# ft232rl_breakout.net
KiCad netlist of a schematic drawn in EAGLE
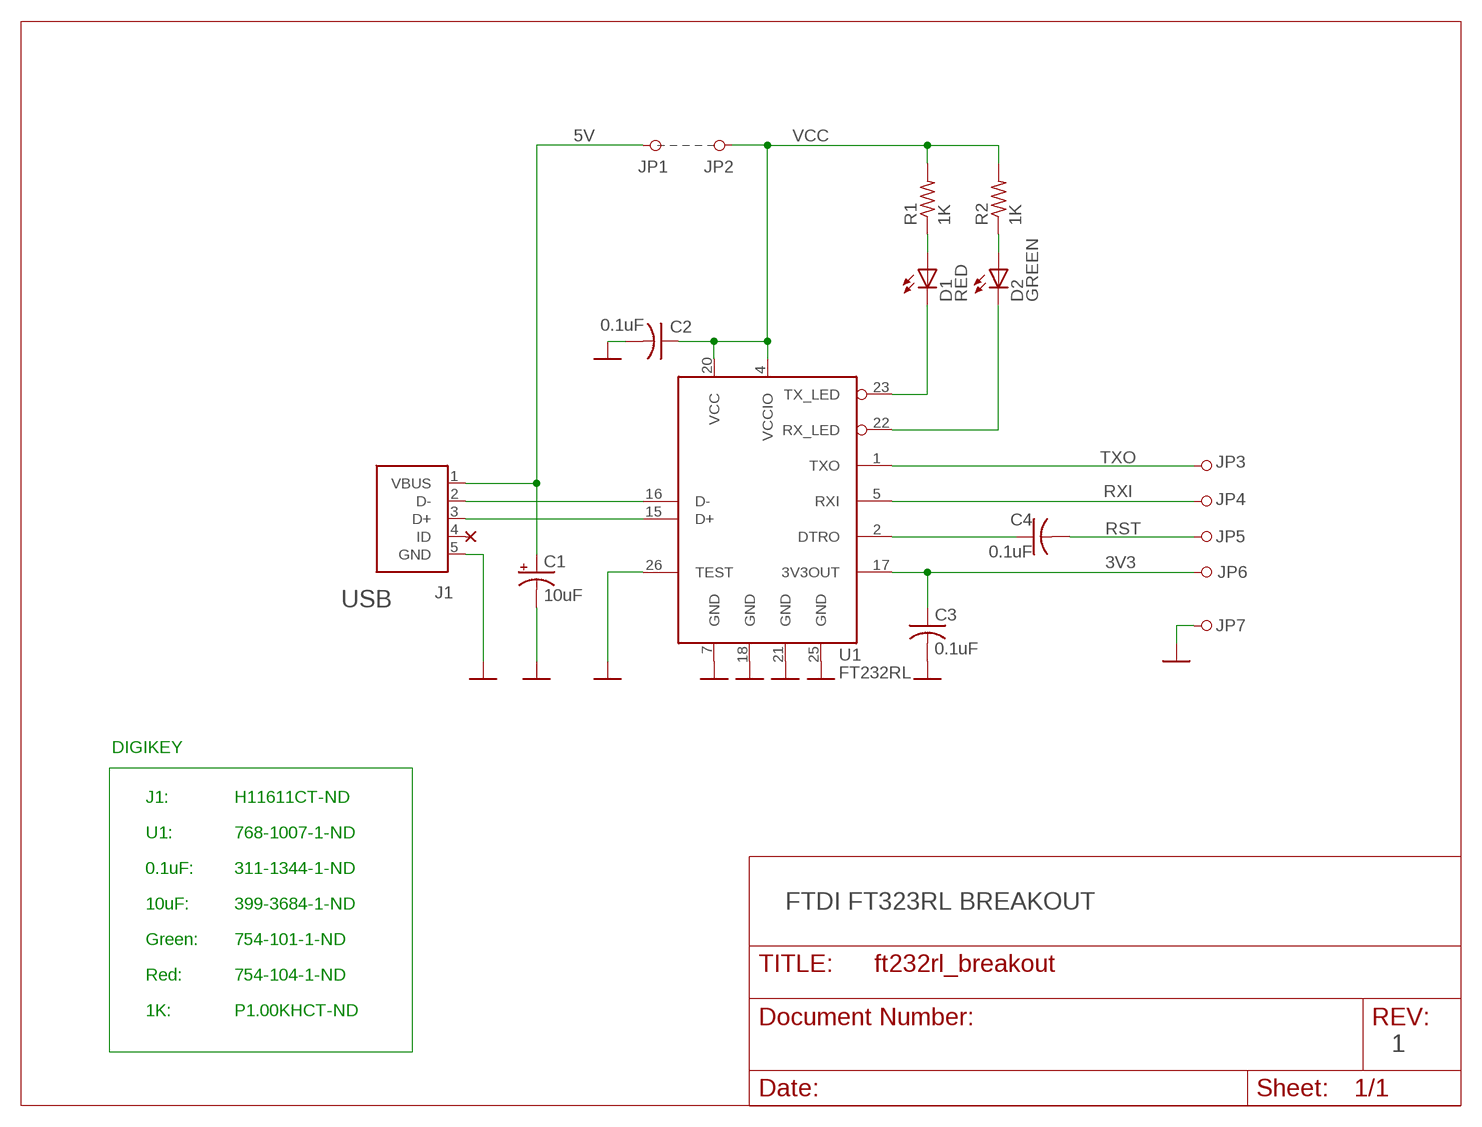
[diagram p0: schematic, sheet 1]

(export (version "E")
  (design (tool "Eeschema 10.0.6"))
  (components
    (comp (ref "C1")
      (value "10uF")
      (footprint "eagle-import:A_3216-18R")
      (libsource (lib "eagle-import") (part "CPOL-USA/3216-18R"))
    )
    (comp (ref "C2")
      (value "0.1uF")
      (footprint "eagle-import:C0402K")
      (libsource (lib "eagle-import") (part "C-USC0402K"))
    )
    (comp (ref "C3")
      (value "0.1uF")
      (footprint "eagle-import:C0402K")
      (libsource (lib "eagle-import") (part "C-USC0402K"))
    )
    (comp (ref "C4")
      (value "0.1uF")
      (footprint "eagle-import:C0402K")
      (libsource (lib "eagle-import") (part "C-USC0402K"))
    )
    (comp (ref "D1")
      (value "RED")
      (footprint "eagle-import:LED_0402")
      (libsource (lib "eagle-import") (part "LED"))
    )
    (comp (ref "D2")
      (value "GREEN")
      (footprint "eagle-import:LED_0402")
      (libsource (lib "eagle-import") (part "LED"))
    )
    (comp (ref "J1")
      (value "USB")
      (footprint "eagle-import:USB-MICRO-ZX62RD-AB-5P8")
      (libsource (lib "eagle-import") (part "USB"))
    )
    (comp (ref "JP1")
      (value "PINHD-1X1")
      (footprint "eagle-import:1X01")
      (libsource (lib "eagle-import") (part "PINHD-1X1"))
    )
    (comp (ref "JP2")
      (value "PINHD-1X1")
      (footprint "eagle-import:1X01")
      (libsource (lib "eagle-import") (part "PINHD-1X1"))
    )
    (comp (ref "JP3")
      (value "PINHD-1X1")
      (footprint "eagle-import:1X01")
      (libsource (lib "eagle-import") (part "PINHD-1X1"))
    )
    (comp (ref "JP4")
      (value "PINHD-1X1")
      (footprint "eagle-import:1X01")
      (libsource (lib "eagle-import") (part "PINHD-1X1"))
    )
    (comp (ref "JP5")
      (value "PINHD-1X1")
      (footprint "eagle-import:1X01")
      (libsource (lib "eagle-import") (part "PINHD-1X1"))
    )
    (comp (ref "JP6")
      (value "PINHD-1X1")
      (footprint "eagle-import:1X01")
      (libsource (lib "eagle-import") (part "PINHD-1X1"))
    )
    (comp (ref "JP7")
      (value "PINHD-1X1")
      (footprint "eagle-import:1X01")
      (libsource (lib "eagle-import") (part "PINHD-1X1"))
    )
    (comp (ref "R1")
      (value "1K")
      (footprint "eagle-import:R0402")
      (libsource (lib "eagle-import") (part "R-US_R0402"))
    )
    (comp (ref "R2")
      (value "1K")
      (footprint "eagle-import:R0402")
      (libsource (lib "eagle-import") (part "R-US_R0402"))
    )
    (comp (ref "U1")
      (value "FT232RL")
      (footprint "eagle-import:SSOP28DB")
      (libsource (lib "eagle-import") (part "FT232RL"))
    )
  )
  (nets
    (net (code "1") (name "/3V3") (class "Default")
      (node (ref "C3") (pin "1") (pinfunction "1_1") (pintype "passive"))
      (node (ref "JP6") (pin "1") (pinfunction "1_1") (pintype "passive"))
      (node (ref "U1") (pin "17") (pinfunction "3V3OUT_17") (pintype "power_in"))
    )
    (net (code "2") (name "/5V") (class "Default")
      (node (ref "C1") (pin "+") (pinfunction "+_+") (pintype "passive"))
      (node (ref "J1") (pin "1") (pinfunction "VBUS_1") (pintype "bidirectional"))
      (node (ref "JP1") (pin "1") (pinfunction "1_1") (pintype "passive"))
    )
    (net (code "3") (name "/RST") (class "Default")
      (node (ref "C4") (pin "2") (pinfunction "2_2") (pintype "passive"))
      (node (ref "JP5") (pin "1") (pinfunction "1_1") (pintype "passive"))
    )
    (net (code "4") (name "/RXI") (class "Default")
      (node (ref "JP4") (pin "1") (pinfunction "1_1") (pintype "passive"))
      (node (ref "U1") (pin "5") (pinfunction "RXI_5") (pintype "input"))
    )
    (net (code "5") (name "/TXO") (class "Default")
      (node (ref "JP3") (pin "1") (pinfunction "1_1") (pintype "passive"))
      (node (ref "U1") (pin "1") (pinfunction "TXO_1") (pintype "output"))
    )
    (net (code "6") (name "/VCC") (class "Default")
      (node (ref "C2") (pin "1") (pinfunction "1_1") (pintype "passive"))
      (node (ref "JP2") (pin "1") (pinfunction "1_1") (pintype "passive"))
      (node (ref "R1") (pin "2") (pinfunction "2_2") (pintype "passive"))
      (node (ref "R2") (pin "2") (pinfunction "2_2") (pintype "passive"))
      (node (ref "U1") (pin "20") (pinfunction "VCC_20") (pintype "power_in"))
      (node (ref "U1") (pin "4") (pinfunction "VCCIO_4") (pintype "power_in"))
    )
    (net (code "7") (name "GND") (class "Default")
      (node (ref "C1") (pin "-") (pinfunction "-_-") (pintype "passive"))
      (node (ref "C2") (pin "2") (pinfunction "2_2") (pintype "passive"))
      (node (ref "C3") (pin "2") (pinfunction "2_2") (pintype "passive"))
      (node (ref "J1") (pin "5") (pinfunction "GND_5") (pintype "bidirectional"))
      (node (ref "JP7") (pin "1") (pinfunction "1_1") (pintype "passive"))
      (node (ref "U1") (pin "18") (pinfunction "GND_18") (pintype "power_in"))
      (node (ref "U1") (pin "21") (pinfunction "GND_21") (pintype "power_in"))
      (node (ref "U1") (pin "25") (pinfunction "GND_25") (pintype "power_in"))
      (node (ref "U1") (pin "26") (pinfunction "TEST_26") (pintype "input"))
      (node (ref "U1") (pin "7") (pinfunction "GND_7") (pintype "power_in"))
    )
    (net (code "8") (name "Net-(D1-PadA)") (class "Default")
      (node (ref "D1") (pin "A") (pinfunction "A_A") (pintype "passive"))
      (node (ref "R1") (pin "1") (pinfunction "1_1") (pintype "passive"))
    )
    (net (code "9") (name "Net-(D2-PadA)") (class "Default")
      (node (ref "D2") (pin "A") (pinfunction "A_A") (pintype "passive"))
      (node (ref "R2") (pin "1") (pinfunction "1_1") (pintype "passive"))
    )
    (net (code "10") (name "Net-(J1-D+)") (class "Default")
      (node (ref "J1") (pin "3") (pinfunction "D+_3") (pintype "bidirectional"))
      (node (ref "U1") (pin "15") (pinfunction "D+_15") (pintype "passive"))
    )
    (net (code "11") (name "Net-(J1-D-)") (class "Default")
      (node (ref "J1") (pin "2") (pinfunction "D-_2") (pintype "bidirectional"))
      (node (ref "U1") (pin "16") (pinfunction "D-_16") (pintype "passive"))
    )
    (net (code "12") (name "Net-(U1-DTRO)") (class "Default")
      (node (ref "C4") (pin "1") (pinfunction "1_1") (pintype "passive"))
      (node (ref "U1") (pin "2") (pinfunction "DTRO_2") (pintype "output"))
    )
    (net (code "13") (name "Net-(U1-RX_LED)") (class "Default")
      (node (ref "D2") (pin "C") (pinfunction "C_C") (pintype "passive"))
      (node (ref "U1") (pin "22") (pinfunction "RX_LED_22") (pintype "output"))
    )
    (net (code "14") (name "Net-(U1-TX_LED)") (class "Default")
      (node (ref "D1") (pin "C") (pinfunction "C_C") (pintype "passive"))
      (node (ref "U1") (pin "23") (pinfunction "TX_LED_23") (pintype "output"))
    )
    (net (code "15") (name "unconnected-(J1-ID-Pad4)") (class "Default")
      (node (ref "J1") (pin "4") (pinfunction "ID_4") (pintype "bidirectional"))
    )
  )
)
